# Amplifier.net
KiCad netlist of a schematic drawn in Altium Designer
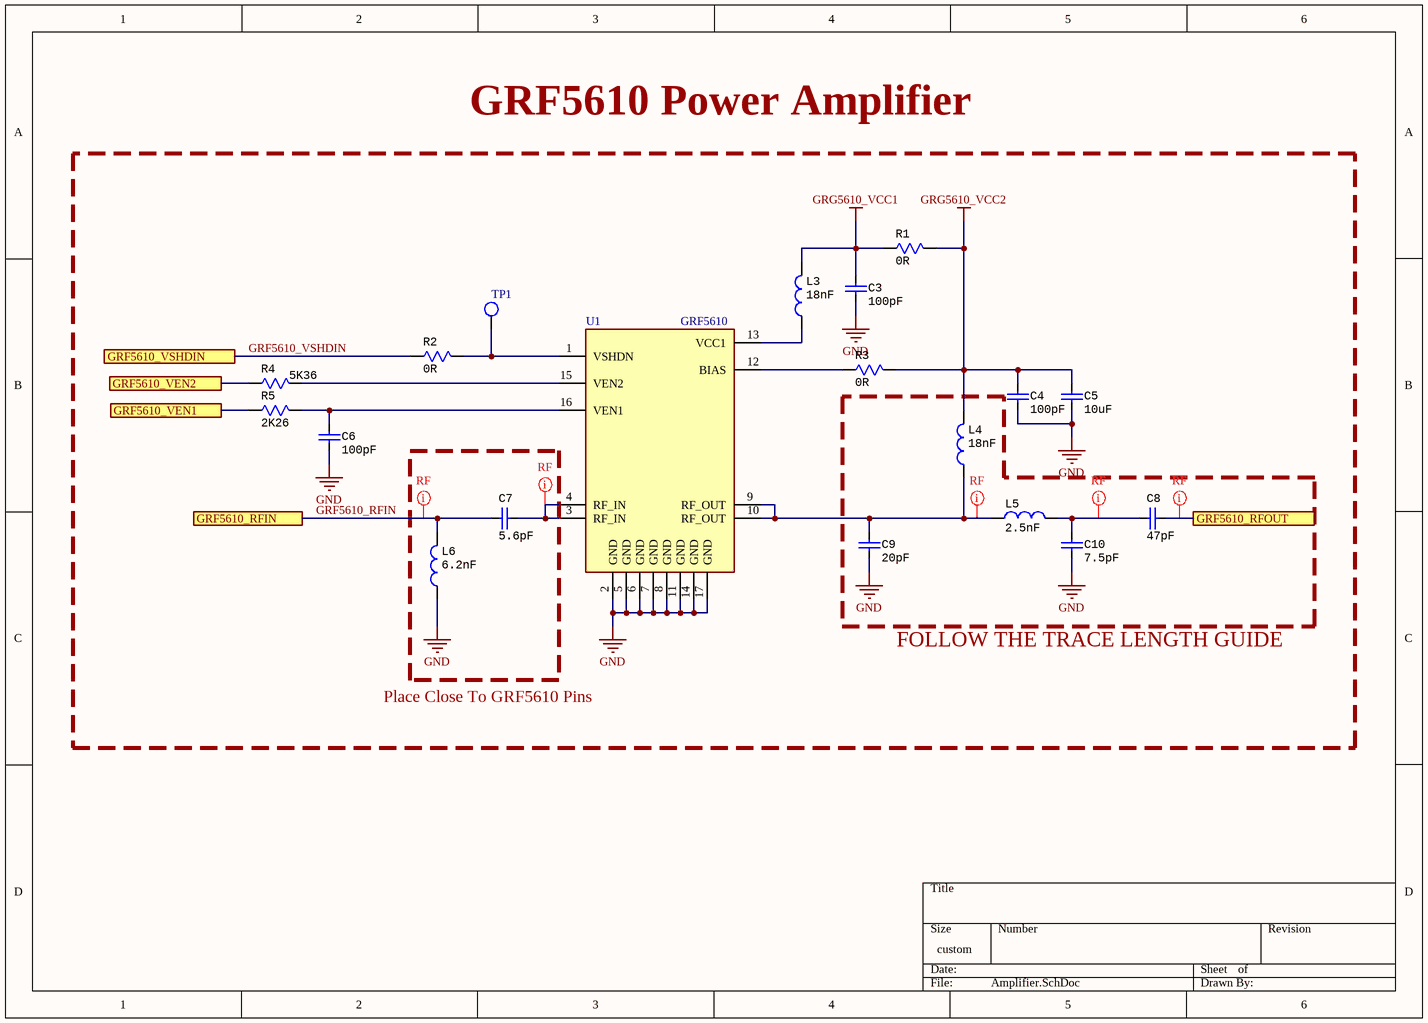
[diagram p0: Amplifier.SchDoc]

(export (version "E")
  (design (tool "Eeschema 10.0.6"))
  (components
    (comp (ref "C3")
      (value "100pF")
      (footprint "CAP Ceramic SMD 0402")
      (description "CAP CER 100pF 50V C0G 0402")
      (fields
        (field (name "MANUFACTURER") "muRata")
        (field (name "MANUFACTURER PART NUMBER") "GRM1555C1H101JA01D")
      )
      (libsource (lib "RFOUT DaughterBoard") (part "CAP 0402 100pF 50V"))
    )
    (comp (ref "C4")
      (value "100pF")
      (footprint "CAP Ceramic SMD 0402")
      (description "CAP CER 100pF 50V C0G 0402")
      (fields
        (field (name "MANUFACTURER") "muRata")
        (field (name "MANUFACTURER PART NUMBER") "GRM1555C1H101JA01D")
      )
      (libsource (lib "RFOUT DaughterBoard") (part "CAP 0402 100pF 50V"))
    )
    (comp (ref "C5")
      (value "10uF")
      (footprint "CAP Ceramic SMD 0402")
      (description "CAP CER 10uF 6.3V X6S")
      (fields
        (field (name "MANUFACTURER") "muRata")
        (field (name "MANUFACTURER PART NUMBER") "GRT155C80J106ME13D")
      )
      (libsource (lib "RFOUT DaughterBoard") (part "CAP 0402 10uF 6.3V"))
    )
    (comp (ref "C6")
      (value "100pF")
      (footprint "CAP Ceramic SMD 0402")
      (description "CAP CER 100pF 50V C0G 0402")
      (fields
        (field (name "MANUFACTURER") "muRata")
        (field (name "MANUFACTURER PART NUMBER") "GRM1555C1H101JA01D")
      )
      (libsource (lib "RFOUT DaughterBoard") (part "CAP 0402 100pF 50V"))
    )
    (comp (ref "C7")
      (value "5.6pF")
      (footprint "CAP Ceramic SMD 0402")
      (description "CAP CER 5.6pF 50V C0G 0402")
      (fields
        (field (name "MANUFACTURER") "muRata")
        (field (name "MANUFACTURER PART NUMBER") "GJM1555C1H5R6BB01D")
      )
      (libsource (lib "RFOUT DaughterBoard") (part "CAP 0402 5.6pF 50V"))
    )
    (comp (ref "C8")
      (value "47pF")
      (footprint "CAP Ceramic SMD 0402")
      (description "CAP CER 47pF 50V C0G 0402")
      (fields
        (field (name "MANUFACTURER") "muRata")
        (field (name "MANUFACTURER PART NUMBER") "GJM1555C1H470GB01D")
      )
      (libsource (lib "RFOUT DaughterBoard") (part "CAP 0402 47pF 50V"))
    )
    (comp (ref "C9")
      (value "20pF")
      (footprint "CAP Ceramic SMD 0402")
      (description "CAP CER 20pF 50V C0G 0402")
      (fields
        (field (name "MANUFACTURER") "muRata")
        (field (name "MANUFACTURER PART NUMBER") "GJM1555C1H200GB01D")
      )
      (libsource (lib "RFOUT DaughterBoard") (part "CAP 0402 20pF 50V"))
    )
    (comp (ref "C10")
      (value "7.5pF")
      (footprint "CAP Ceramic SMD 0402")
      (description "CAP CER 7.5pF 50V C0G 0402")
      (fields
        (field (name "MANUFACTURER") "muRata")
        (field (name "MANUFACTURER PART NUMBER") "GJM1555C1H7R5BB01D")
      )
      (libsource (lib "RFOUT DaughterBoard") (part "CAP 0402 7.5pF 50V"))
    )
    (comp (ref "L3")
      (value "18nF")
      (footprint "IND SMD 0603")
      (description "FIXED IND 18nH 1.4A 75mΩ 0603")
      (fields
        (field (name "MANUFACTURER") "muRata")
        (field (name "MANUFACTURER PART NUMBER") "LQW18AN18NG8ZD")
      )
      (libsource (lib "RFOUT DaughterBoard") (part "IND 0603 18nH"))
    )
    (comp (ref "L4")
      (value "18nF")
      (footprint "IND SMD 0402HP")
      (description "900mA 18nH ±5% 120mΩ Wire-wound chip inductor 0402 Fixed Inductors RoHS")
      (fields
        (field (name "MANUFACTURER") "Coilcraft")
        (field (name "MANUFACTURER PART NUMBER") "0402HP-18NXJRW")
      )
      (libsource (lib "RFOUT DaughterBoard") (part "IND 0402 18nH"))
    )
    (comp (ref "L5")
      (value "2.5nF")
      (footprint "IND SMD 0402")
      (description "FIXED IND 2.5nH 2.1A 30mΩ 0402")
      (fields
        (field (name "MANUFACTURER") "muRata")
        (field (name "MANUFACTURER PART NUMBER") "LQW15AN2N5G80D")
      )
      (libsource (lib "RFOUT DaughterBoard") (part "IND 0402 2.5nH"))
    )
    (comp (ref "L6")
      (value "6.2nF")
      (footprint "IND SMD 0402")
      (description "FIXED IND 6.2nH 700mA 90mΩ 0402")
      (fields
        (field (name "MANUFACTURER") "muRata")
        (field (name "MANUFACTURER PART NUMBER") "LQW15AN6N2C00D")
      )
      (libsource (lib "RFOUT DaughterBoard") (part "IND 0402 6.2nH"))
    )
    (comp (ref "R1")
      (value "0R")
      (footprint "RES SMD 0603")
      (description "100mW Thick Film Resistors 75V ±5% 0Ω 0603 Chip Resistor - Surface Mount ROHS")
      (fields
        (field (name "MANUFACTURER") "YAGEO")
        (field (name "MANUFACTURER PART NUMBER") "RC0603JR-070RL")
      )
      (libsource (lib "RFOUT DaughterBoard") (part "RES 0603 0R 1%"))
    )
    (comp (ref "R2")
      (value "0R")
      (footprint "RES SMD 0603")
      (description "100mW Thick Film Resistors 75V ±5% 0Ω 0603 Chip Resistor - Surface Mount ROHS")
      (fields
        (field (name "MANUFACTURER") "YAGEO")
        (field (name "MANUFACTURER PART NUMBER") "RC0603JR-070RL")
      )
      (libsource (lib "RFOUT DaughterBoard") (part "RES 0603 0R 1%"))
    )
    (comp (ref "R3")
      (value "0R")
      (footprint "RES SMD 0603")
      (description "100mW Thick Film Resistors 75V ±5% 0Ω 0603 Chip Resistor - Surface Mount ROHS")
      (fields
        (field (name "MANUFACTURER") "YAGEO")
        (field (name "MANUFACTURER PART NUMBER") "RC0603JR-070RL")
      )
      (libsource (lib "RFOUT DaughterBoard") (part "RES 0603 0R 1%"))
    )
    (comp (ref "R4")
      (value "5K36")
      (footprint "CAP Ceramic SMD 0402")
      (description "RES 5.36kΩ ±1% 100mW 0402")
      (fields
        (field (name "MANUFACTURER") "PANASONIC")
        (field (name "MANUFACTURER PART NUMBER") "ERJ2RKF5361X")
      )
      (libsource (lib "RFOUT DaughterBoard") (part "RES 0402 5K36 1%"))
    )
    (comp (ref "R5")
      (value "2K26")
      (footprint "CAP Ceramic SMD 0402")
      (description "RES 2.26kΩ ±0.1% 62.5mW 0402")
      (fields
        (field (name "MANUFACTURER") "YAGEO")
        (field (name "MANUFACTURER PART NUMBER") "RT0402BRD072K26L")
      )
      (libsource (lib "RFOUT DaughterBoard") (part "RES 0402 2k26 0.1%"))
    )
    (comp (ref "TP1")
      (value "TestPoint")
      (footprint "TestPoint Surface 0.8mm")
      (libsource (lib "RFOUT DaughterBoard") (part "TestPoint"))
    )
    (comp (ref "U1")
      (value "GRF5610")
      (footprint "QFN50P300X300X80-17N")
      (libsource (lib "RFOUT DaughterBoard") (part "GRF5610"))
    )
  )
  (nets
    (net (code "1") (name "/GRF5610_RFIN") (class "Default")
      (node (ref "C7") (pin "1") (pinfunction "1_1") (pintype "passive"))
      (node (ref "L6") (pin "1") (pinfunction "1_1") (pintype "passive"))
    )
    (net (code "2") (name "/GRF5610_RFOUT") (class "Default")
      (node (ref "C8") (pin "2") (pinfunction "2_2") (pintype "passive"))
    )
    (net (code "3") (name "/GRF5610_VEN1") (class "Default")
      (node (ref "R5") (pin "1") (pinfunction "1_1") (pintype "passive"))
    )
    (net (code "4") (name "/GRF5610_VEN2") (class "Default")
      (node (ref "R4") (pin "1") (pinfunction "1_1") (pintype "passive"))
    )
    (net (code "5") (name "/GRF5610_VSHDIN") (class "Default")
      (node (ref "R2") (pin "1") (pinfunction "1_1") (pintype "passive"))
    )
    (net (code "6") (name "GND") (class "Default")
      (node (ref "C10") (pin "2") (pinfunction "2_2") (pintype "passive"))
      (node (ref "C3") (pin "2") (pinfunction "2_2") (pintype "passive"))
      (node (ref "C4") (pin "2") (pinfunction "2_2") (pintype "passive"))
      (node (ref "C5") (pin "2") (pinfunction "2_2") (pintype "passive"))
      (node (ref "C6") (pin "2") (pinfunction "2_2") (pintype "passive"))
      (node (ref "C9") (pin "2") (pinfunction "2_2") (pintype "passive"))
      (node (ref "L6") (pin "2") (pinfunction "2_2") (pintype "passive"))
      (node (ref "U1") (pin "11") (pinfunction "GND_11") (pintype "passive"))
      (node (ref "U1") (pin "14") (pinfunction "GND_14") (pintype "passive"))
      (node (ref "U1") (pin "17") (pinfunction "GND_17") (pintype "passive"))
      (node (ref "U1") (pin "2") (pinfunction "GND_2") (pintype "passive"))
      (node (ref "U1") (pin "5") (pinfunction "GND_5") (pintype "passive"))
      (node (ref "U1") (pin "6") (pinfunction "GND_6") (pintype "passive"))
      (node (ref "U1") (pin "7") (pinfunction "GND_7") (pintype "passive"))
      (node (ref "U1") (pin "8") (pinfunction "GND_8") (pintype "passive"))
    )
    (net (code "7") (name "GRG5610_VCC1") (class "Default")
      (node (ref "C3") (pin "1") (pinfunction "1_1") (pintype "passive"))
      (node (ref "L3") (pin "1") (pinfunction "1_1") (pintype "passive"))
      (node (ref "R1") (pin "1") (pinfunction "1_1") (pintype "passive"))
    )
    (net (code "8") (name "GRG5610_VCC2") (class "Default")
      (node (ref "C4") (pin "1") (pinfunction "1_1") (pintype "passive"))
      (node (ref "C5") (pin "1") (pinfunction "1_1") (pintype "passive"))
      (node (ref "L4") (pin "1") (pinfunction "1_1") (pintype "passive"))
      (node (ref "R1") (pin "2") (pinfunction "2_2") (pintype "passive"))
      (node (ref "R3") (pin "2") (pinfunction "2_2") (pintype "passive"))
    )
    (net (code "9") (name "Net-(C7-Pad2)") (class "Default")
      (node (ref "C7") (pin "2") (pinfunction "2_2") (pintype "passive"))
      (node (ref "U1") (pin "3") (pinfunction "RF_IN_3") (pintype "passive"))
      (node (ref "U1") (pin "4") (pinfunction "RF_IN_4") (pintype "passive"))
    )
    (net (code "10") (name "Net-(C9-Pad1)") (class "Default")
      (node (ref "C9") (pin "1") (pinfunction "1_1") (pintype "passive"))
      (node (ref "L4") (pin "2") (pinfunction "2_2") (pintype "passive"))
      (node (ref "L5") (pin "2") (pinfunction "2_2") (pintype "passive"))
      (node (ref "U1") (pin "10") (pinfunction "RF_OUT_10") (pintype "passive"))
      (node (ref "U1") (pin "9") (pinfunction "RF_OUT_9") (pintype "passive"))
    )
    (net (code "11") (name "Net-(C10-Pad1)") (class "Default")
      (node (ref "C10") (pin "1") (pinfunction "1_1") (pintype "passive"))
      (node (ref "C8") (pin "1") (pinfunction "1_1") (pintype "passive"))
      (node (ref "L5") (pin "1") (pinfunction "1_1") (pintype "passive"))
    )
    (net (code "12") (name "Net-(U1-BIAS)") (class "Default")
      (node (ref "R3") (pin "1") (pinfunction "1_1") (pintype "passive"))
      (node (ref "U1") (pin "12") (pinfunction "BIAS_12") (pintype "passive"))
    )
    (net (code "13") (name "Net-(U1-VCC1)") (class "Default")
      (node (ref "L3") (pin "2") (pinfunction "2_2") (pintype "passive"))
      (node (ref "U1") (pin "13") (pinfunction "VCC1_13") (pintype "passive"))
    )
    (net (code "14") (name "Net-(U1-VEN1)") (class "Default")
      (node (ref "C6") (pin "1") (pinfunction "1_1") (pintype "passive"))
      (node (ref "R5") (pin "2") (pinfunction "2_2") (pintype "passive"))
      (node (ref "U1") (pin "16") (pinfunction "VEN1_16") (pintype "passive"))
    )
    (net (code "15") (name "Net-(U1-VEN2)") (class "Default")
      (node (ref "R4") (pin "2") (pinfunction "2_2") (pintype "passive"))
      (node (ref "U1") (pin "15") (pinfunction "VEN2_15") (pintype "passive"))
    )
    (net (code "16") (name "Net-(U1-VSHDN)") (class "Default")
      (node (ref "R2") (pin "2") (pinfunction "2_2") (pintype "passive"))
      (node (ref "TP1") (pin "1") (pinfunction "1_1") (pintype "passive"))
      (node (ref "U1") (pin "1") (pinfunction "VSHDN_1") (pintype "passive"))
    )
  )
)
